# signal-board_v1_23.net
KiCad netlist of a schematic drawn in EAGLE
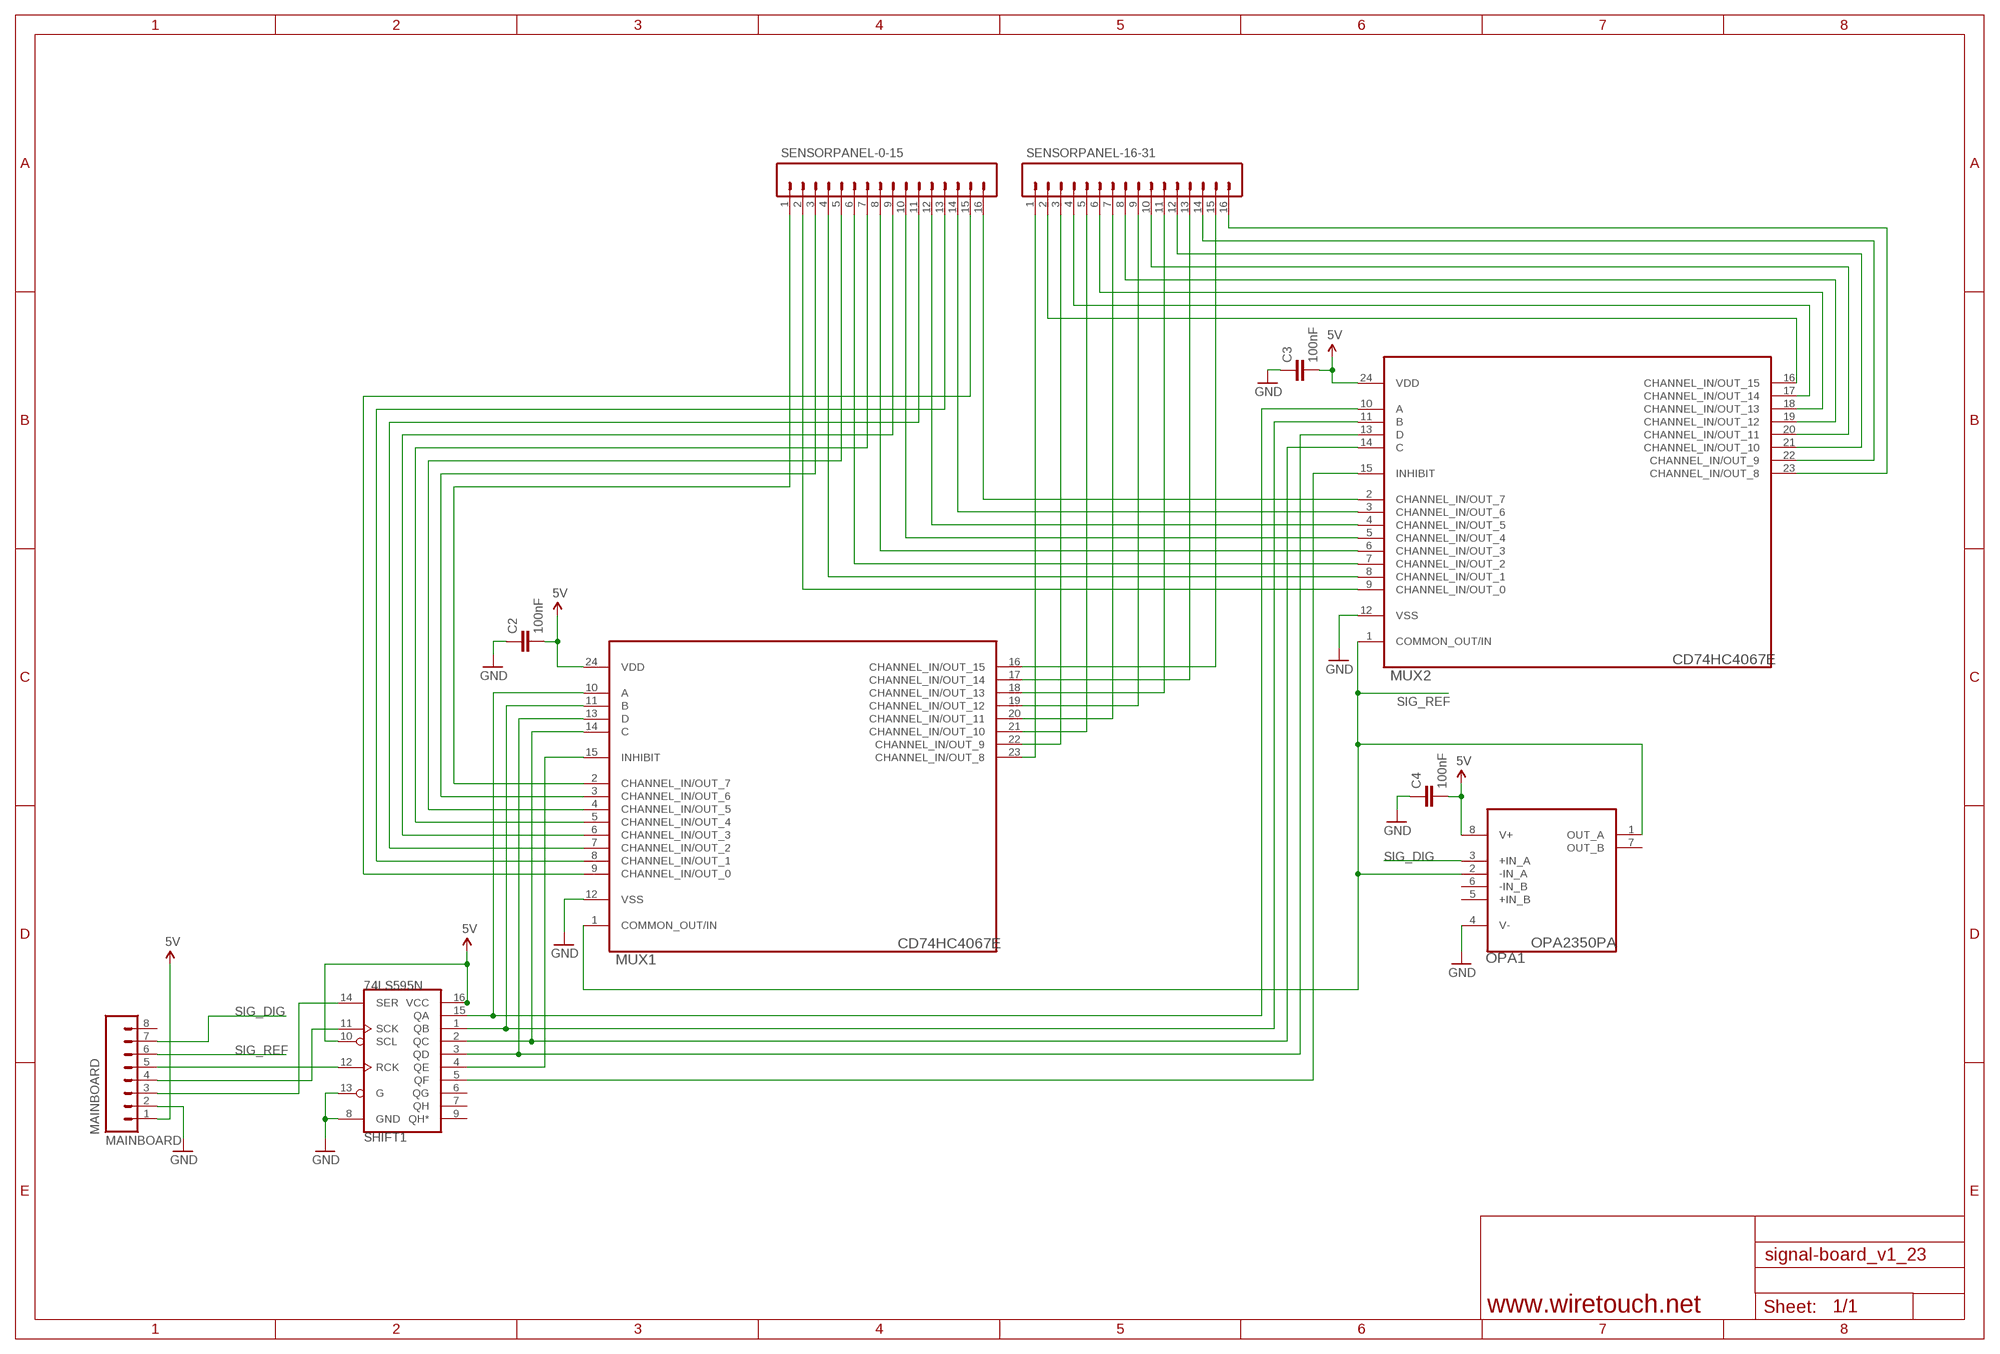
[diagram p0: schematic, sheet 1]

(export (version "E")
  (design (tool "Eeschema 10.0.6"))
  (components
    (comp (ref "C2")
      (value "100nF")
      (footprint "eagle-import:CAP-PTH-SMALL")
      (libsource (lib "eagle-import") (part "CAPPTH"))
    )
    (comp (ref "C3")
      (value "100nF")
      (footprint "eagle-import:CAP-PTH-SMALL")
      (libsource (lib "eagle-import") (part "CAPPTH"))
    )
    (comp (ref "C4")
      (value "100nF")
      (footprint "eagle-import:CAP-PTH-SMALL")
      (libsource (lib "eagle-import") (part "CAPPTH"))
    )
    (comp (ref "MAINBOARD")
      (value "MAINBOARD")
      (footprint "eagle-import:1X08_LONGPADS")
      (libsource (lib "eagle-import") (part "M08LONGPADS"))
    )
    (comp (ref "MUX1")
      (value "CD74HC4067E")
      (footprint "eagle-import:PDIP24-WIDE-CD74HC4067E")
      (libsource (lib "eagle-import") (part "CD74HC4067E"))
    )
    (comp (ref "MUX2")
      (value "CD74HC4067E")
      (footprint "eagle-import:PDIP24-WIDE-CD74HC4067E")
      (libsource (lib "eagle-import") (part "CD74HC4067E"))
    )
    (comp (ref "OPA1")
      (value "OPA2350PA")
      (footprint "eagle-import:DIP254P762X508-8")
      (libsource (lib "eagle-import") (part "OPA2350PA"))
    )
    (comp (ref "SENSORPANEL-0-15")
      (value "M16LOCK_LONGPADS")
      (footprint "eagle-import:1X16_LOCK_LONGPADS")
      (libsource (lib "eagle-import") (part "M16LOCK_LONGPADS"))
    )
    (comp (ref "SENSORPANEL-16-31")
      (value "M16LOCK_LONGPADS")
      (footprint "eagle-import:1X16_LOCK_LONGPADS")
      (libsource (lib "eagle-import") (part "M16LOCK_LONGPADS"))
    )
    (comp (ref "SHIFT1")
      (value "74LS595N")
      (footprint "eagle-import:DIL16")
      (libsource (lib "eagle-import") (part "74595NLS"))
    )
  )
  (nets
    (net (code "1") (name "/SIG_DIG") (class "Default")
      (node (ref "MAINBOARD") (pin "7") (pinfunction "7_7") (pintype "passive"))
      (node (ref "OPA1") (pin "3") (pinfunction "+IN_A_3") (pintype "input"))
    )
    (net (code "2") (name "/SIG_REF") (class "Default")
      (node (ref "MAINBOARD") (pin "6") (pinfunction "6_6") (pintype "passive"))
      (node (ref "MUX1") (pin "1") (pinfunction "COMMON_OUT/IN_1") (pintype "passive"))
      (node (ref "MUX2") (pin "1") (pinfunction "COMMON_OUT/IN_1") (pintype "passive"))
      (node (ref "OPA1") (pin "1") (pinfunction "OUT_A_1") (pintype "output"))
      (node (ref "OPA1") (pin "2") (pinfunction "-IN_A_2") (pintype "input"))
    )
    (net (code "3") (name "5V") (class "Default")
      (node (ref "C2") (pin "2") (pinfunction "2_2") (pintype "passive"))
      (node (ref "C3") (pin "2") (pinfunction "2_2") (pintype "passive"))
      (node (ref "C4") (pin "2") (pinfunction "2_2") (pintype "passive"))
      (node (ref "MAINBOARD") (pin "1") (pinfunction "1_1") (pintype "passive"))
      (node (ref "MUX1") (pin "24") (pinfunction "VDD_24") (pintype "power_in"))
      (node (ref "MUX2") (pin "24") (pinfunction "VDD_24") (pintype "power_in"))
      (node (ref "OPA1") (pin "8") (pinfunction "V+_8") (pintype "power_in"))
      (node (ref "SHIFT1") (pin "10") (pinfunction "SCL_10") (pintype "input"))
      (node (ref "SHIFT1") (pin "16") (pinfunction "VCC_16") (pintype "power_in"))
    )
    (net (code "4") (name "GND") (class "Default")
      (node (ref "C2") (pin "1") (pinfunction "1_1") (pintype "passive"))
      (node (ref "C3") (pin "1") (pinfunction "1_1") (pintype "passive"))
      (node (ref "C4") (pin "1") (pinfunction "1_1") (pintype "passive"))
      (node (ref "MAINBOARD") (pin "2") (pinfunction "2_2") (pintype "passive"))
      (node (ref "MUX1") (pin "12") (pinfunction "VSS_12") (pintype "power_in"))
      (node (ref "MUX2") (pin "12") (pinfunction "VSS_12") (pintype "power_in"))
      (node (ref "OPA1") (pin "4") (pinfunction "V-_4") (pintype "power_in"))
      (node (ref "SHIFT1") (pin "13") (pinfunction "G_13") (pintype "input"))
      (node (ref "SHIFT1") (pin "8") (pinfunction "GND_8") (pintype "power_in"))
    )
    (net (code "5") (name "Net-(MUX1-A)") (class "Default")
      (node (ref "MUX1") (pin "10") (pinfunction "A_10") (pintype "input"))
      (node (ref "MUX2") (pin "10") (pinfunction "A_10") (pintype "input"))
      (node (ref "SHIFT1") (pin "15") (pinfunction "QA_15") (pintype "tri_state"))
    )
    (net (code "6") (name "Net-(MUX1-B)") (class "Default")
      (node (ref "MUX1") (pin "11") (pinfunction "B_11") (pintype "input"))
      (node (ref "MUX2") (pin "11") (pinfunction "B_11") (pintype "input"))
      (node (ref "SHIFT1") (pin "1") (pinfunction "QB_1") (pintype "tri_state"))
    )
    (net (code "7") (name "Net-(MUX1-C)") (class "Default")
      (node (ref "MUX1") (pin "14") (pinfunction "C_14") (pintype "input"))
      (node (ref "MUX2") (pin "14") (pinfunction "C_14") (pintype "input"))
      (node (ref "SHIFT1") (pin "2") (pinfunction "QC_2") (pintype "tri_state"))
    )
    (net (code "8") (name "Net-(MUX1-CHANNEL_IN{slash}OUT_0)") (class "Default")
      (node (ref "MUX1") (pin "9") (pinfunction "CHANNEL_IN/OUT_0_9") (pintype "bidirectional"))
      (node (ref "SENSORPANEL-0-15") (pin "15") (pinfunction "15_15") (pintype "passive"))
    )
    (net (code "9") (name "Net-(MUX1-CHANNEL_IN{slash}OUT_1)") (class "Default")
      (node (ref "MUX1") (pin "8") (pinfunction "CHANNEL_IN/OUT_1_8") (pintype "bidirectional"))
      (node (ref "SENSORPANEL-0-15") (pin "13") (pinfunction "13_13") (pintype "passive"))
    )
    (net (code "10") (name "Net-(MUX1-CHANNEL_IN{slash}OUT_2)") (class "Default")
      (node (ref "MUX1") (pin "7") (pinfunction "CHANNEL_IN/OUT_2_7") (pintype "bidirectional"))
      (node (ref "SENSORPANEL-0-15") (pin "11") (pinfunction "11_11") (pintype "passive"))
    )
    (net (code "11") (name "Net-(MUX1-CHANNEL_IN{slash}OUT_3)") (class "Default")
      (node (ref "MUX1") (pin "6") (pinfunction "CHANNEL_IN/OUT_3_6") (pintype "bidirectional"))
      (node (ref "SENSORPANEL-0-15") (pin "9") (pinfunction "9_9") (pintype "passive"))
    )
    (net (code "12") (name "Net-(MUX1-CHANNEL_IN{slash}OUT_4)") (class "Default")
      (node (ref "MUX1") (pin "5") (pinfunction "CHANNEL_IN/OUT_4_5") (pintype "bidirectional"))
      (node (ref "SENSORPANEL-0-15") (pin "7") (pinfunction "7_7") (pintype "passive"))
    )
    (net (code "13") (name "Net-(MUX1-CHANNEL_IN{slash}OUT_5)") (class "Default")
      (node (ref "MUX1") (pin "4") (pinfunction "CHANNEL_IN/OUT_5_4") (pintype "bidirectional"))
      (node (ref "SENSORPANEL-0-15") (pin "5") (pinfunction "5_5") (pintype "passive"))
    )
    (net (code "14") (name "Net-(MUX1-CHANNEL_IN{slash}OUT_6)") (class "Default")
      (node (ref "MUX1") (pin "3") (pinfunction "CHANNEL_IN/OUT_6_3") (pintype "bidirectional"))
      (node (ref "SENSORPANEL-0-15") (pin "3") (pinfunction "3_3") (pintype "passive"))
    )
    (net (code "15") (name "Net-(MUX1-CHANNEL_IN{slash}OUT_7)") (class "Default")
      (node (ref "MUX1") (pin "2") (pinfunction "CHANNEL_IN/OUT_7_2") (pintype "bidirectional"))
      (node (ref "SENSORPANEL-0-15") (pin "1") (pinfunction "1_1") (pintype "passive"))
    )
    (net (code "16") (name "Net-(MUX1-CHANNEL_IN{slash}OUT_8)") (class "Default")
      (node (ref "MUX1") (pin "23") (pinfunction "CHANNEL_IN/OUT_8_23") (pintype "bidirectional"))
      (node (ref "SENSORPANEL-16-31") (pin "1") (pinfunction "1_1") (pintype "passive"))
    )
    (net (code "17") (name "Net-(MUX1-CHANNEL_IN{slash}OUT_9)") (class "Default")
      (node (ref "MUX1") (pin "22") (pinfunction "CHANNEL_IN/OUT_9_22") (pintype "bidirectional"))
      (node (ref "SENSORPANEL-16-31") (pin "3") (pinfunction "3_3") (pintype "passive"))
    )
    (net (code "18") (name "Net-(MUX1-CHANNEL_IN{slash}OUT_10)") (class "Default")
      (node (ref "MUX1") (pin "21") (pinfunction "CHANNEL_IN/OUT_10_21") (pintype "bidirectional"))
      (node (ref "SENSORPANEL-16-31") (pin "5") (pinfunction "5_5") (pintype "passive"))
    )
    (net (code "19") (name "Net-(MUX1-CHANNEL_IN{slash}OUT_11)") (class "Default")
      (node (ref "MUX1") (pin "20") (pinfunction "CHANNEL_IN/OUT_11_20") (pintype "bidirectional"))
      (node (ref "SENSORPANEL-16-31") (pin "7") (pinfunction "7_7") (pintype "passive"))
    )
    (net (code "20") (name "Net-(MUX1-CHANNEL_IN{slash}OUT_12)") (class "Default")
      (node (ref "MUX1") (pin "19") (pinfunction "CHANNEL_IN/OUT_12_19") (pintype "bidirectional"))
      (node (ref "SENSORPANEL-16-31") (pin "9") (pinfunction "9_9") (pintype "passive"))
    )
    (net (code "21") (name "Net-(MUX1-CHANNEL_IN{slash}OUT_13)") (class "Default")
      (node (ref "MUX1") (pin "18") (pinfunction "CHANNEL_IN/OUT_13_18") (pintype "bidirectional"))
      (node (ref "SENSORPANEL-16-31") (pin "11") (pinfunction "11_11") (pintype "passive"))
    )
    (net (code "22") (name "Net-(MUX1-CHANNEL_IN{slash}OUT_14)") (class "Default")
      (node (ref "MUX1") (pin "17") (pinfunction "CHANNEL_IN/OUT_14_17") (pintype "bidirectional"))
      (node (ref "SENSORPANEL-16-31") (pin "13") (pinfunction "13_13") (pintype "passive"))
    )
    (net (code "23") (name "Net-(MUX1-CHANNEL_IN{slash}OUT_15)") (class "Default")
      (node (ref "MUX1") (pin "16") (pinfunction "CHANNEL_IN/OUT_15_16") (pintype "bidirectional"))
      (node (ref "SENSORPANEL-16-31") (pin "15") (pinfunction "15_15") (pintype "passive"))
    )
    (net (code "24") (name "Net-(MUX1-D)") (class "Default")
      (node (ref "MUX1") (pin "13") (pinfunction "D_13") (pintype "input"))
      (node (ref "MUX2") (pin "13") (pinfunction "D_13") (pintype "input"))
      (node (ref "SHIFT1") (pin "3") (pinfunction "QD_3") (pintype "tri_state"))
    )
    (net (code "25") (name "Net-(MUX1-INHIBIT)") (class "Default")
      (node (ref "MUX1") (pin "15") (pinfunction "INHIBIT_15") (pintype "input"))
      (node (ref "SHIFT1") (pin "4") (pinfunction "QE_4") (pintype "tri_state"))
    )
    (net (code "26") (name "Net-(MUX2-CHANNEL_IN{slash}OUT_0)") (class "Default")
      (node (ref "MUX2") (pin "9") (pinfunction "CHANNEL_IN/OUT_0_9") (pintype "bidirectional"))
      (node (ref "SENSORPANEL-0-15") (pin "2") (pinfunction "2_2") (pintype "passive"))
    )
    (net (code "27") (name "Net-(MUX2-CHANNEL_IN{slash}OUT_1)") (class "Default")
      (node (ref "MUX2") (pin "8") (pinfunction "CHANNEL_IN/OUT_1_8") (pintype "bidirectional"))
      (node (ref "SENSORPANEL-0-15") (pin "4") (pinfunction "4_4") (pintype "passive"))
    )
    (net (code "28") (name "Net-(MUX2-CHANNEL_IN{slash}OUT_2)") (class "Default")
      (node (ref "MUX2") (pin "7") (pinfunction "CHANNEL_IN/OUT_2_7") (pintype "bidirectional"))
      (node (ref "SENSORPANEL-0-15") (pin "6") (pinfunction "6_6") (pintype "passive"))
    )
    (net (code "29") (name "Net-(MUX2-CHANNEL_IN{slash}OUT_3)") (class "Default")
      (node (ref "MUX2") (pin "6") (pinfunction "CHANNEL_IN/OUT_3_6") (pintype "bidirectional"))
      (node (ref "SENSORPANEL-0-15") (pin "8") (pinfunction "8_8") (pintype "passive"))
    )
    (net (code "30") (name "Net-(MUX2-CHANNEL_IN{slash}OUT_4)") (class "Default")
      (node (ref "MUX2") (pin "5") (pinfunction "CHANNEL_IN/OUT_4_5") (pintype "bidirectional"))
      (node (ref "SENSORPANEL-0-15") (pin "10") (pinfunction "10_10") (pintype "passive"))
    )
    (net (code "31") (name "Net-(MUX2-CHANNEL_IN{slash}OUT_5)") (class "Default")
      (node (ref "MUX2") (pin "4") (pinfunction "CHANNEL_IN/OUT_5_4") (pintype "bidirectional"))
      (node (ref "SENSORPANEL-0-15") (pin "12") (pinfunction "12_12") (pintype "passive"))
    )
    (net (code "32") (name "Net-(MUX2-CHANNEL_IN{slash}OUT_6)") (class "Default")
      (node (ref "MUX2") (pin "3") (pinfunction "CHANNEL_IN/OUT_6_3") (pintype "bidirectional"))
      (node (ref "SENSORPANEL-0-15") (pin "14") (pinfunction "14_14") (pintype "passive"))
    )
    (net (code "33") (name "Net-(MUX2-CHANNEL_IN{slash}OUT_7)") (class "Default")
      (node (ref "MUX2") (pin "2") (pinfunction "CHANNEL_IN/OUT_7_2") (pintype "bidirectional"))
      (node (ref "SENSORPANEL-0-15") (pin "16") (pinfunction "16_16") (pintype "passive"))
    )
    (net (code "34") (name "Net-(MUX2-CHANNEL_IN{slash}OUT_8)") (class "Default")
      (node (ref "MUX2") (pin "23") (pinfunction "CHANNEL_IN/OUT_8_23") (pintype "bidirectional"))
      (node (ref "SENSORPANEL-16-31") (pin "16") (pinfunction "16_16") (pintype "passive"))
    )
    (net (code "35") (name "Net-(MUX2-CHANNEL_IN{slash}OUT_9)") (class "Default")
      (node (ref "MUX2") (pin "22") (pinfunction "CHANNEL_IN/OUT_9_22") (pintype "bidirectional"))
      (node (ref "SENSORPANEL-16-31") (pin "14") (pinfunction "14_14") (pintype "passive"))
    )
    (net (code "36") (name "Net-(MUX2-CHANNEL_IN{slash}OUT_10)") (class "Default")
      (node (ref "MUX2") (pin "21") (pinfunction "CHANNEL_IN/OUT_10_21") (pintype "bidirectional"))
      (node (ref "SENSORPANEL-16-31") (pin "12") (pinfunction "12_12") (pintype "passive"))
    )
    (net (code "37") (name "Net-(MUX2-CHANNEL_IN{slash}OUT_11)") (class "Default")
      (node (ref "MUX2") (pin "20") (pinfunction "CHANNEL_IN/OUT_11_20") (pintype "bidirectional"))
      (node (ref "SENSORPANEL-16-31") (pin "10") (pinfunction "10_10") (pintype "passive"))
    )
    (net (code "38") (name "Net-(MUX2-CHANNEL_IN{slash}OUT_12)") (class "Default")
      (node (ref "MUX2") (pin "19") (pinfunction "CHANNEL_IN/OUT_12_19") (pintype "bidirectional"))
      (node (ref "SENSORPANEL-16-31") (pin "8") (pinfunction "8_8") (pintype "passive"))
    )
    (net (code "39") (name "Net-(MUX2-CHANNEL_IN{slash}OUT_13)") (class "Default")
      (node (ref "MUX2") (pin "18") (pinfunction "CHANNEL_IN/OUT_13_18") (pintype "bidirectional"))
      (node (ref "SENSORPANEL-16-31") (pin "6") (pinfunction "6_6") (pintype "passive"))
    )
    (net (code "40") (name "Net-(MUX2-CHANNEL_IN{slash}OUT_14)") (class "Default")
      (node (ref "MUX2") (pin "17") (pinfunction "CHANNEL_IN/OUT_14_17") (pintype "bidirectional"))
      (node (ref "SENSORPANEL-16-31") (pin "4") (pinfunction "4_4") (pintype "passive"))
    )
    (net (code "41") (name "Net-(MUX2-CHANNEL_IN{slash}OUT_15)") (class "Default")
      (node (ref "MUX2") (pin "16") (pinfunction "CHANNEL_IN/OUT_15_16") (pintype "bidirectional"))
      (node (ref "SENSORPANEL-16-31") (pin "2") (pinfunction "2_2") (pintype "passive"))
    )
    (net (code "42") (name "Net-(MUX2-INHIBIT)") (class "Default")
      (node (ref "MUX2") (pin "15") (pinfunction "INHIBIT_15") (pintype "input"))
      (node (ref "SHIFT1") (pin "5") (pinfunction "QF_5") (pintype "tri_state"))
    )
    (net (code "43") (name "Net-(SHIFT1-RCK)") (class "Default")
      (node (ref "MAINBOARD") (pin "5") (pinfunction "5_5") (pintype "passive"))
      (node (ref "SHIFT1") (pin "12") (pinfunction "RCK_12") (pintype "input"))
    )
    (net (code "44") (name "Net-(SHIFT1-SCK)") (class "Default")
      (node (ref "MAINBOARD") (pin "4") (pinfunction "4_4") (pintype "passive"))
      (node (ref "SHIFT1") (pin "11") (pinfunction "SCK_11") (pintype "input"))
    )
    (net (code "45") (name "Net-(SHIFT1-SER)") (class "Default")
      (node (ref "MAINBOARD") (pin "3") (pinfunction "3_3") (pintype "passive"))
      (node (ref "SHIFT1") (pin "14") (pinfunction "SER_14") (pintype "input"))
    )
    (net (code "46") (name "unconnected-(MAINBOARD-Pad8)") (class "Default")
      (node (ref "MAINBOARD") (pin "8") (pinfunction "8_8") (pintype "passive"))
    )
    (net (code "47") (name "unconnected-(OPA1-+IN_B-Pad5)") (class "Default")
      (node (ref "OPA1") (pin "5") (pinfunction "+IN_B_5") (pintype "input"))
    )
    (net (code "48") (name "unconnected-(OPA1--IN_B-Pad6)") (class "Default")
      (node (ref "OPA1") (pin "6") (pinfunction "-IN_B_6") (pintype "input"))
    )
    (net (code "49") (name "unconnected-(OPA1-OUT_B-Pad7)") (class "Default")
      (node (ref "OPA1") (pin "7") (pinfunction "OUT_B_7") (pintype "output"))
    )
    (net (code "50") (name "unconnected-(SHIFT1-QG-Pad6)") (class "Default")
      (node (ref "SHIFT1") (pin "6") (pinfunction "QG_6") (pintype "tri_state"))
    )
    (net (code "51") (name "unconnected-(SHIFT1-QH*-Pad9)") (class "Default")
      (node (ref "SHIFT1") (pin "9") (pinfunction "QH*_9") (pintype "tri_state"))
    )
    (net (code "52") (name "unconnected-(SHIFT1-QH-Pad7)") (class "Default")
      (node (ref "SHIFT1") (pin "7") (pinfunction "QH_7") (pintype "tri_state"))
    )
  )
)
